# SCH_BusyCube_2022-06-02.net
KiCad netlist of a schematic drawn in EasyEDA
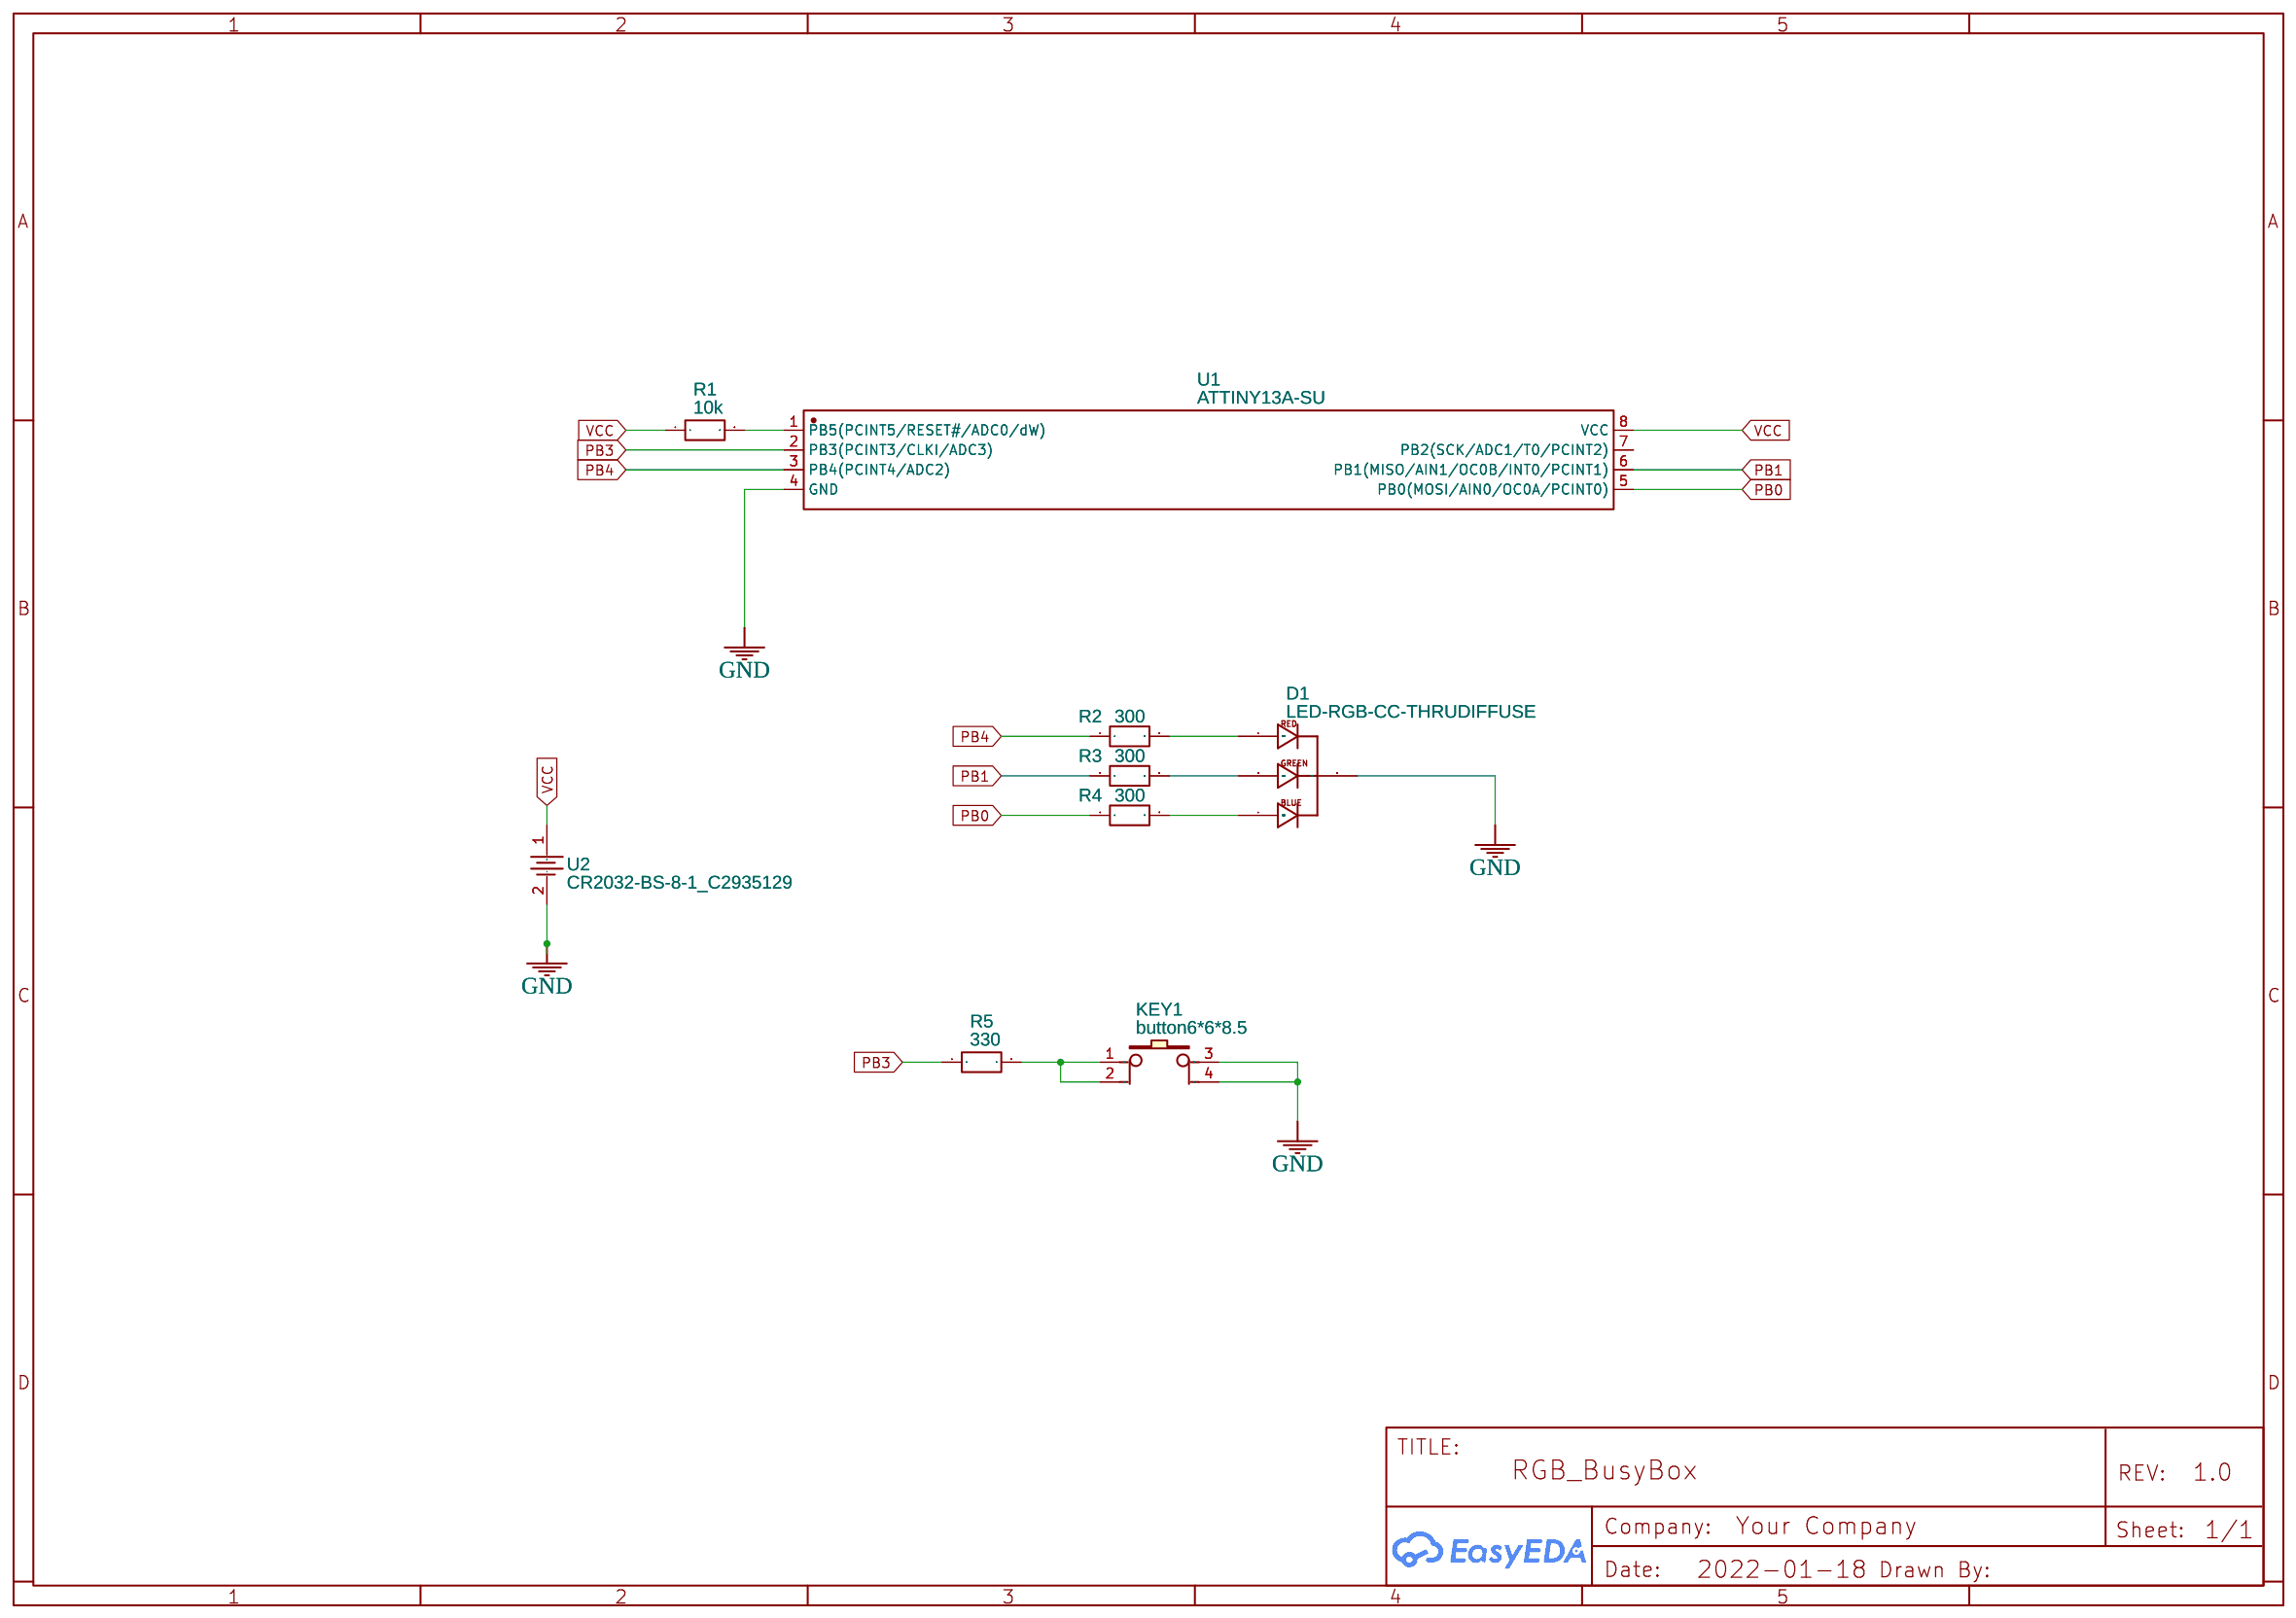
[diagram p0: schematic sheet]

(export (version "E")
  (design (tool "Eeschema 10.0.6"))
  (components
    (comp (ref "D1") (value "LED-RGB-CC-THRUDIFFUSE") (libsource (lib "") (part "LED-RGB-CC-THRUDIFFUSE")))
    (comp (ref "KEY1")
      (value "button6*6*8.5")
      (fields (field (name "BOM_Supplier Part") "C59980"))
      (libsource (lib "") (part "button6*6*8.5"))
    )
    (comp (ref "R1") (value "10k") (libsource (lib "") (part "R_0603_EU")))
    (comp (ref "R2") (value "300") (libsource (lib "") (part "R_0603_EU")))
    (comp (ref "R3") (value "300") (libsource (lib "") (part "R_0603_EU")))
    (comp (ref "R4") (value "300") (libsource (lib "") (part "R_0603_EU")))
    (comp (ref "R5") (value "330") (libsource (lib "") (part "R_0603_EU")))
    (comp (ref "U1")
      (value "ATTINY13A-SU")
      (fields (field (name "BOM_Supplier Part") "C9805"))
      (libsource (lib "") (part "ATTINY13A-SU"))
    )
    (comp (ref "U2")
      (value "CR2032-BS-8-1_C2935129")
      (fields
        (field (name "BOM_Manufacturer Part") "CR2032-BS-8-1")
        (field (name "BOM_Supplier Part") "C2935129")
      )
      (libsource (lib "") (part "CR2032-BS-8-1_C2935129"))
    )
  )
  (nets
    (net (code "1") (name "GND") (class "Default")
      (node (ref "D1") (pin "2") (pinfunction "CATHODE_2") (pintype "unspecified"))
      (node (ref "KEY1") (pin "3") (pinfunction "3_3") (pintype "input"))
      (node (ref "KEY1") (pin "4") (pinfunction "4_4") (pintype "input"))
      (node (ref "U1") (pin "4") (pinfunction "GND_4") (pintype "unspecified"))
      (node (ref "U2") (pin "2") (pinfunction "-_2") (pintype "input"))
    )
    (net (code "2") (name "Net-(D1-BLUE_CATHODE)") (class "Default")
      (node (ref "D1") (pin "4") (pinfunction "BLUE_CATHODE_4") (pintype "unspecified"))
      (node (ref "R4") (pin "2") (pinfunction "2_2") (pintype "unspecified"))
    )
    (net (code "3") (name "Net-(D1-GREEN_CATHODE)") (class "Default")
      (node (ref "D1") (pin "3") (pinfunction "GREEN_CATHODE_3") (pintype "unspecified"))
      (node (ref "R3") (pin "2") (pinfunction "2_2") (pintype "unspecified"))
    )
    (net (code "4") (name "Net-(D1-RED_CATHODE)") (class "Default")
      (node (ref "D1") (pin "1") (pinfunction "RED_CATHODE_1") (pintype "unspecified"))
      (node (ref "R2") (pin "2") (pinfunction "2_2") (pintype "unspecified"))
    )
    (net (code "5") (name "Net-(KEY1-Pad1)") (class "Default")
      (node (ref "KEY1") (pin "1") (pinfunction "1_1") (pintype "input"))
      (node (ref "KEY1") (pin "2") (pinfunction "2_2") (pintype "input"))
      (node (ref "R5") (pin "2") (pinfunction "2_2") (pintype "unspecified"))
    )
    (net (code "6") (name "Net-(U1-PB5(PCINT5{slash}RESET#{slash}ADC0{slash}dW))") (class "Default")
      (node (ref "R1") (pin "2") (pinfunction "2_2") (pintype "unspecified"))
      (node (ref "U1") (pin "1") (pinfunction "PB5(PCINT5/RESET#/ADC0/dW)_1") (pintype "unspecified"))
    )
    (net (code "7") (name "PB0") (class "Default")
      (node (ref "R4") (pin "1") (pinfunction "1_1") (pintype "unspecified"))
      (node (ref "U1") (pin "5") (pinfunction "PB0(MOSI/AIN0/OC0A/PCINT0)_5") (pintype "unspecified"))
    )
    (net (code "8") (name "PB1") (class "Default")
      (node (ref "R3") (pin "1") (pinfunction "1_1") (pintype "unspecified"))
      (node (ref "U1") (pin "6") (pinfunction "PB1(MISO/AIN1/OC0B/INT0/PCINT1)_6") (pintype "unspecified"))
    )
    (net (code "9") (name "PB3") (class "Default")
      (node (ref "R5") (pin "1") (pinfunction "1_1") (pintype "unspecified"))
      (node (ref "U1") (pin "2") (pinfunction "PB3(PCINT3/CLKI/ADC3)_2") (pintype "unspecified"))
    )
    (net (code "10") (name "PB4") (class "Default")
      (node (ref "R2") (pin "1") (pinfunction "1_1") (pintype "unspecified"))
      (node (ref "U1") (pin "3") (pinfunction "PB4(PCINT4/ADC2)_3") (pintype "unspecified"))
    )
    (net (code "11") (name "VCC") (class "Default")
      (node (ref "R1") (pin "1") (pinfunction "1_1") (pintype "unspecified"))
      (node (ref "U1") (pin "8") (pinfunction "VCC_8") (pintype "unspecified"))
      (node (ref "U2") (pin "1") (pinfunction "+_1") (pintype "input"))
    )
    (net (code "12") (name "unconnected-(U1-PB2(SCK{slash}ADC1{slash}T0{slash}PCINT2)-Pad7)") (class "Default")
      (node (ref "U1") (pin "7") (pinfunction "PB2(SCK/ADC1/T0/PCINT2)_7") (pintype "unspecified"))
    )
  )
)
